# RS232_Transciever_MAX232.net
KiCad netlist of a schematic drawn in Altium Designer
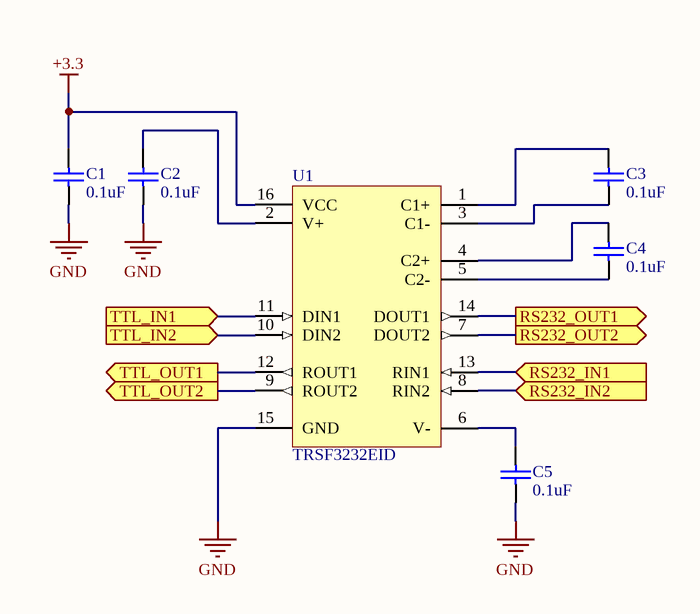
[diagram p0: RS232 Transciever (MAX232).SchDoc]

(export (version "E")
  (design (tool "Eeschema 10.0.6"))
  (components
    (comp (ref "C1")
      (value "0.1uF")
      (footprint "C0603")
      (description "Capacitor")
      (fields (field (name "Comment") "Cap"))
      (libsource (lib "Miscellaneous Devices") (part "Cap"))
    )
    (comp (ref "C2")
      (value "0.1uF")
      (footprint "C0603")
      (description "Capacitor")
      (fields (field (name "Comment") "Cap"))
      (libsource (lib "Miscellaneous Devices") (part "Cap"))
    )
    (comp (ref "C3")
      (value "0.1uF")
      (footprint "C0603")
      (description "Capacitor")
      (fields (field (name "Comment") "Cap"))
      (libsource (lib "Miscellaneous Devices") (part "Cap"))
    )
    (comp (ref "C4")
      (value "0.1uF")
      (footprint "C0603")
      (description "Capacitor")
      (fields (field (name "Comment") "Cap"))
      (libsource (lib "Miscellaneous Devices") (part "Cap"))
    )
    (comp (ref "C5")
      (value "0.1uF")
      (footprint "C0603")
      (description "Capacitor")
      (fields (field (name "Comment") "Cap"))
      (libsource (lib "Miscellaneous Devices") (part "Cap"))
    )
    (comp (ref "U1")
      (value "TRSF3232EID")
      (footprint "SOIC127P600X175-16N")
      (description "TEXAS INSTRUMENTS - TRSF3232EID - RS232, 1MBIT, LINE DRIV/REC, 16SOIC")
      (libsource (lib "TRSF3232EID") (part "TRSF3232EID"))
    )
  )
  (nets
    (net (code "1") (name "+3.3") (class "Default")
      (node (ref "C1") (pin "1") (pinfunction "1_1") (pintype "passive"))
      (node (ref "U1") (pin "16") (pinfunction "VCC_16") (pintype "power_in"))
    )
    (net (code "2") (name "/RS232_IN1") (class "Default")
      (node (ref "U1") (pin "13") (pinfunction "RIN1_13") (pintype "input"))
    )
    (net (code "3") (name "/RS232_IN2") (class "Default")
      (node (ref "U1") (pin "8") (pinfunction "RIN2_8") (pintype "input"))
    )
    (net (code "4") (name "/RS232_OUT1") (class "Default")
      (node (ref "U1") (pin "14") (pinfunction "DOUT1_14") (pintype "output"))
    )
    (net (code "5") (name "/RS232_OUT2") (class "Default")
      (node (ref "U1") (pin "7") (pinfunction "DOUT2_7") (pintype "output"))
    )
    (net (code "6") (name "/TTL_IN1") (class "Default")
      (node (ref "U1") (pin "11") (pinfunction "DIN1_11") (pintype "input"))
    )
    (net (code "7") (name "/TTL_IN2") (class "Default")
      (node (ref "U1") (pin "10") (pinfunction "DIN2_10") (pintype "input"))
    )
    (net (code "8") (name "/TTL_OUT1") (class "Default")
      (node (ref "U1") (pin "12") (pinfunction "ROUT1_12") (pintype "output"))
    )
    (net (code "9") (name "/TTL_OUT2") (class "Default")
      (node (ref "U1") (pin "9") (pinfunction "ROUT2_9") (pintype "output"))
    )
    (net (code "10") (name "GND") (class "Default")
      (node (ref "C1") (pin "2") (pinfunction "2_2") (pintype "passive"))
      (node (ref "C2") (pin "2") (pinfunction "2_2") (pintype "passive"))
      (node (ref "C5") (pin "2") (pinfunction "2_2") (pintype "passive"))
      (node (ref "U1") (pin "15") (pinfunction "GND_15") (pintype "power_in"))
    )
    (net (code "11") (name "Net-(U1-C1+)") (class "Default")
      (node (ref "C3") (pin "1") (pinfunction "1_1") (pintype "passive"))
      (node (ref "U1") (pin "1") (pinfunction "C1+_1") (pintype "passive"))
    )
    (net (code "12") (name "Net-(U1-C1-)") (class "Default")
      (node (ref "C3") (pin "2") (pinfunction "2_2") (pintype "passive"))
      (node (ref "U1") (pin "3") (pinfunction "C1-_3") (pintype "passive"))
    )
    (net (code "13") (name "Net-(U1-C2+)") (class "Default")
      (node (ref "C4") (pin "1") (pinfunction "1_1") (pintype "passive"))
      (node (ref "U1") (pin "4") (pinfunction "C2+_4") (pintype "passive"))
    )
    (net (code "14") (name "Net-(U1-C2-)") (class "Default")
      (node (ref "C4") (pin "2") (pinfunction "2_2") (pintype "passive"))
      (node (ref "U1") (pin "5") (pinfunction "C2-_5") (pintype "passive"))
    )
    (net (code "15") (name "Net-(U1-V+)") (class "Default")
      (node (ref "C2") (pin "1") (pinfunction "1_1") (pintype "passive"))
      (node (ref "U1") (pin "2") (pinfunction "V+_2") (pintype "passive"))
    )
    (net (code "16") (name "Net-(U1-V-)") (class "Default")
      (node (ref "C5") (pin "1") (pinfunction "1_1") (pintype "passive"))
      (node (ref "U1") (pin "6") (pinfunction "V-_6") (pintype "passive"))
    )
  )
)
